# DC309A_PowerSupplies.net
KiCad netlist of a schematic drawn in Altium Designer
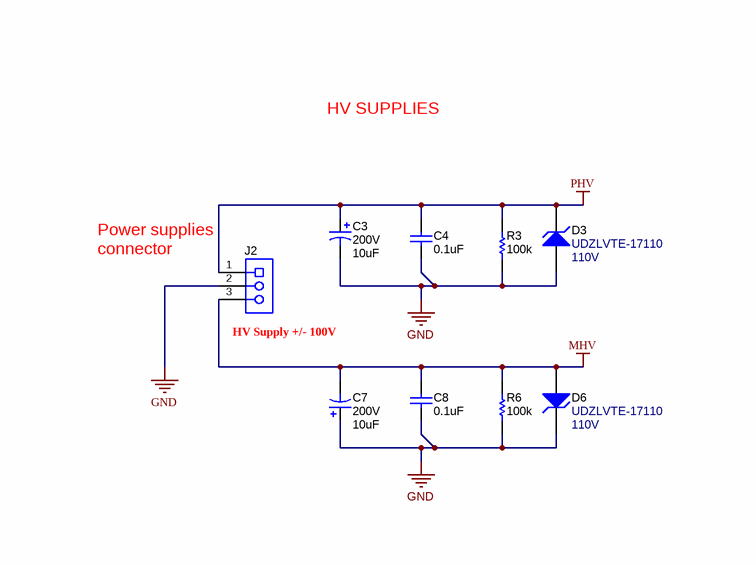
[diagram p0: DC309A_PowerSupplies.SchDoc, top left]
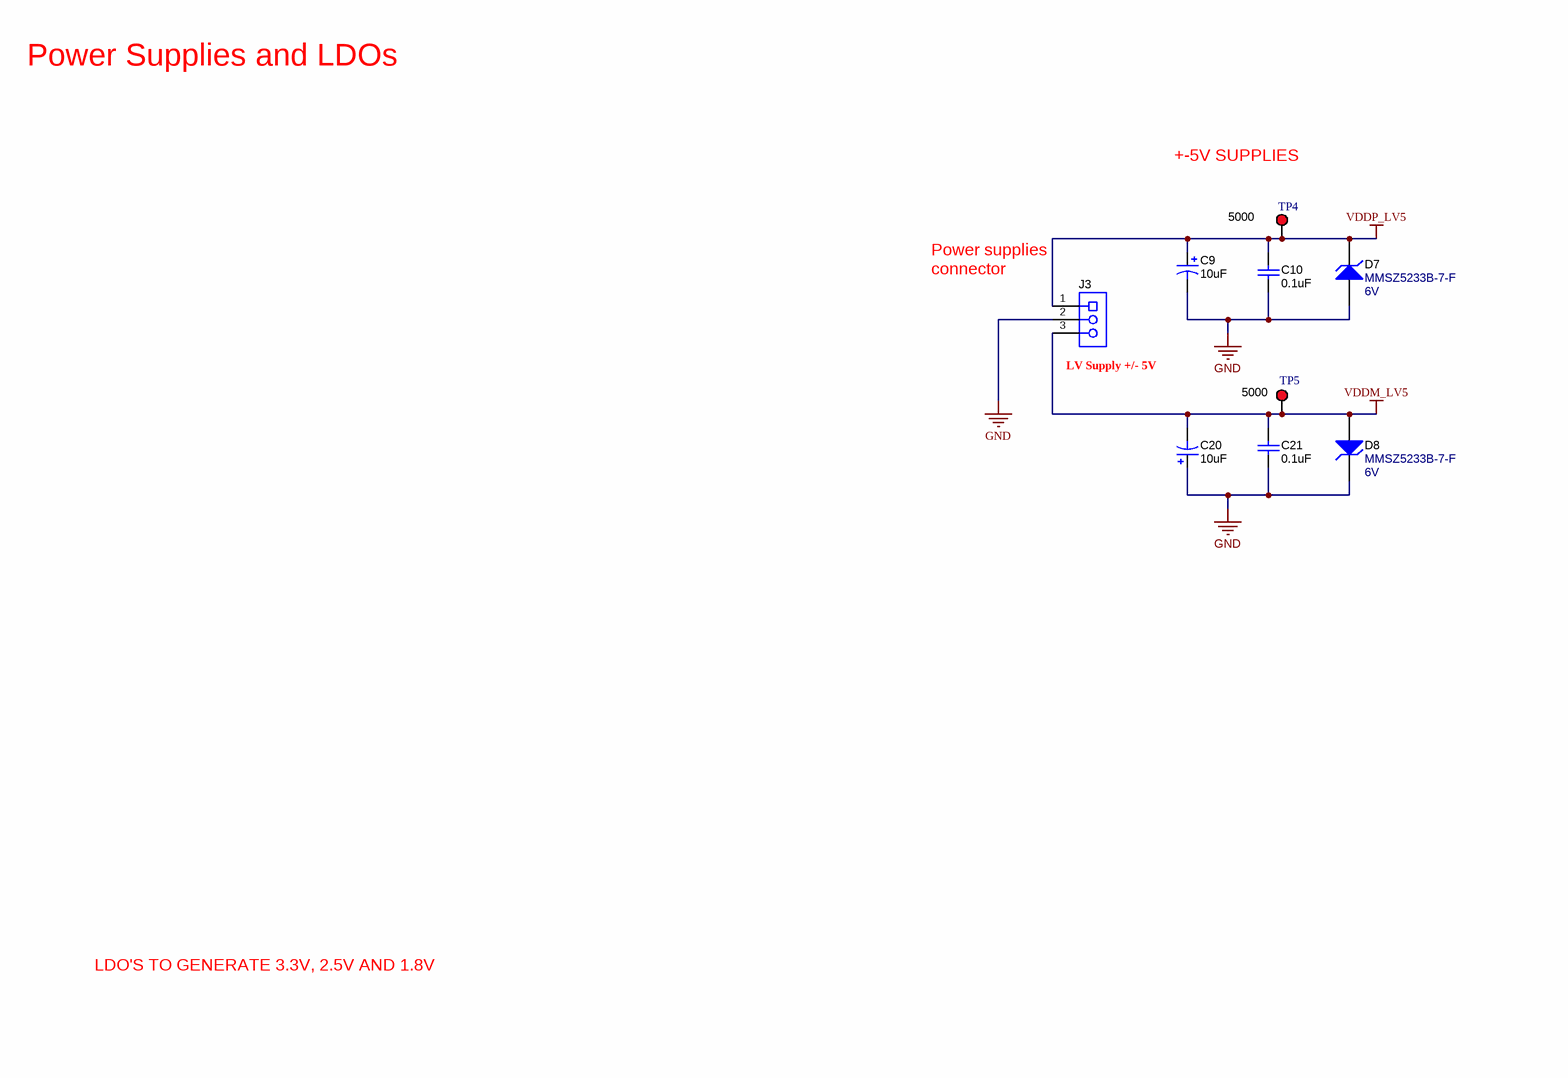
[diagram p1: DC309A_PowerSupplies.SchDoc, top right]
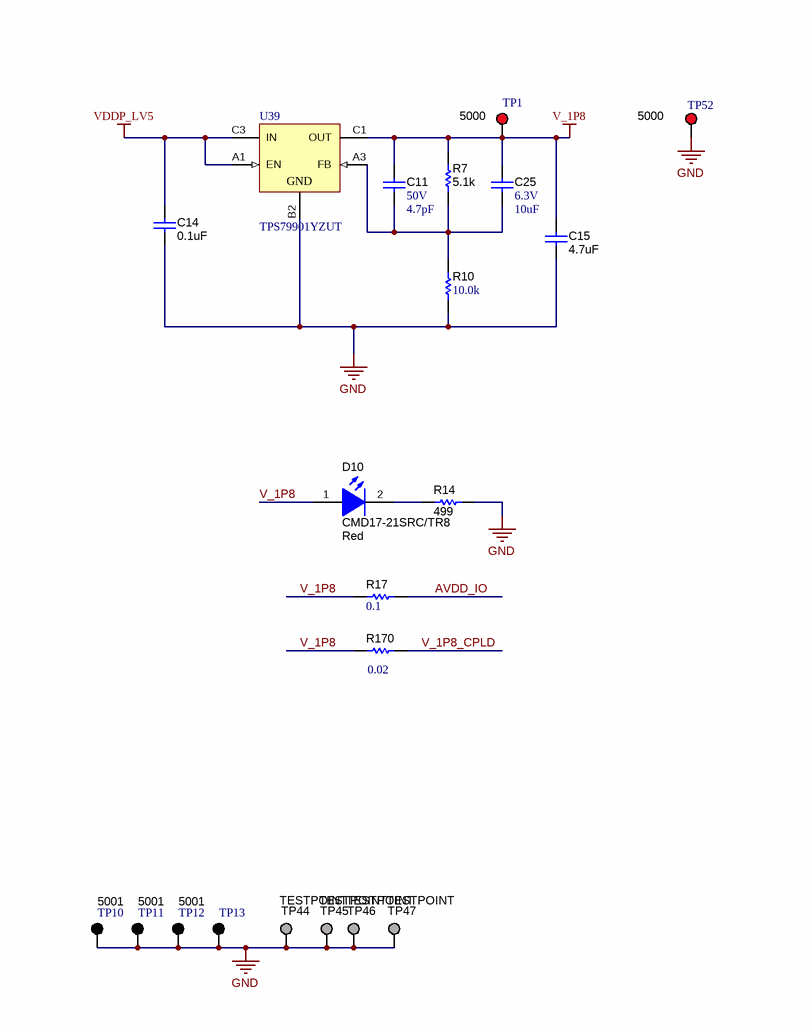
[diagram p2: DC309A_PowerSupplies.SchDoc, bottom left]
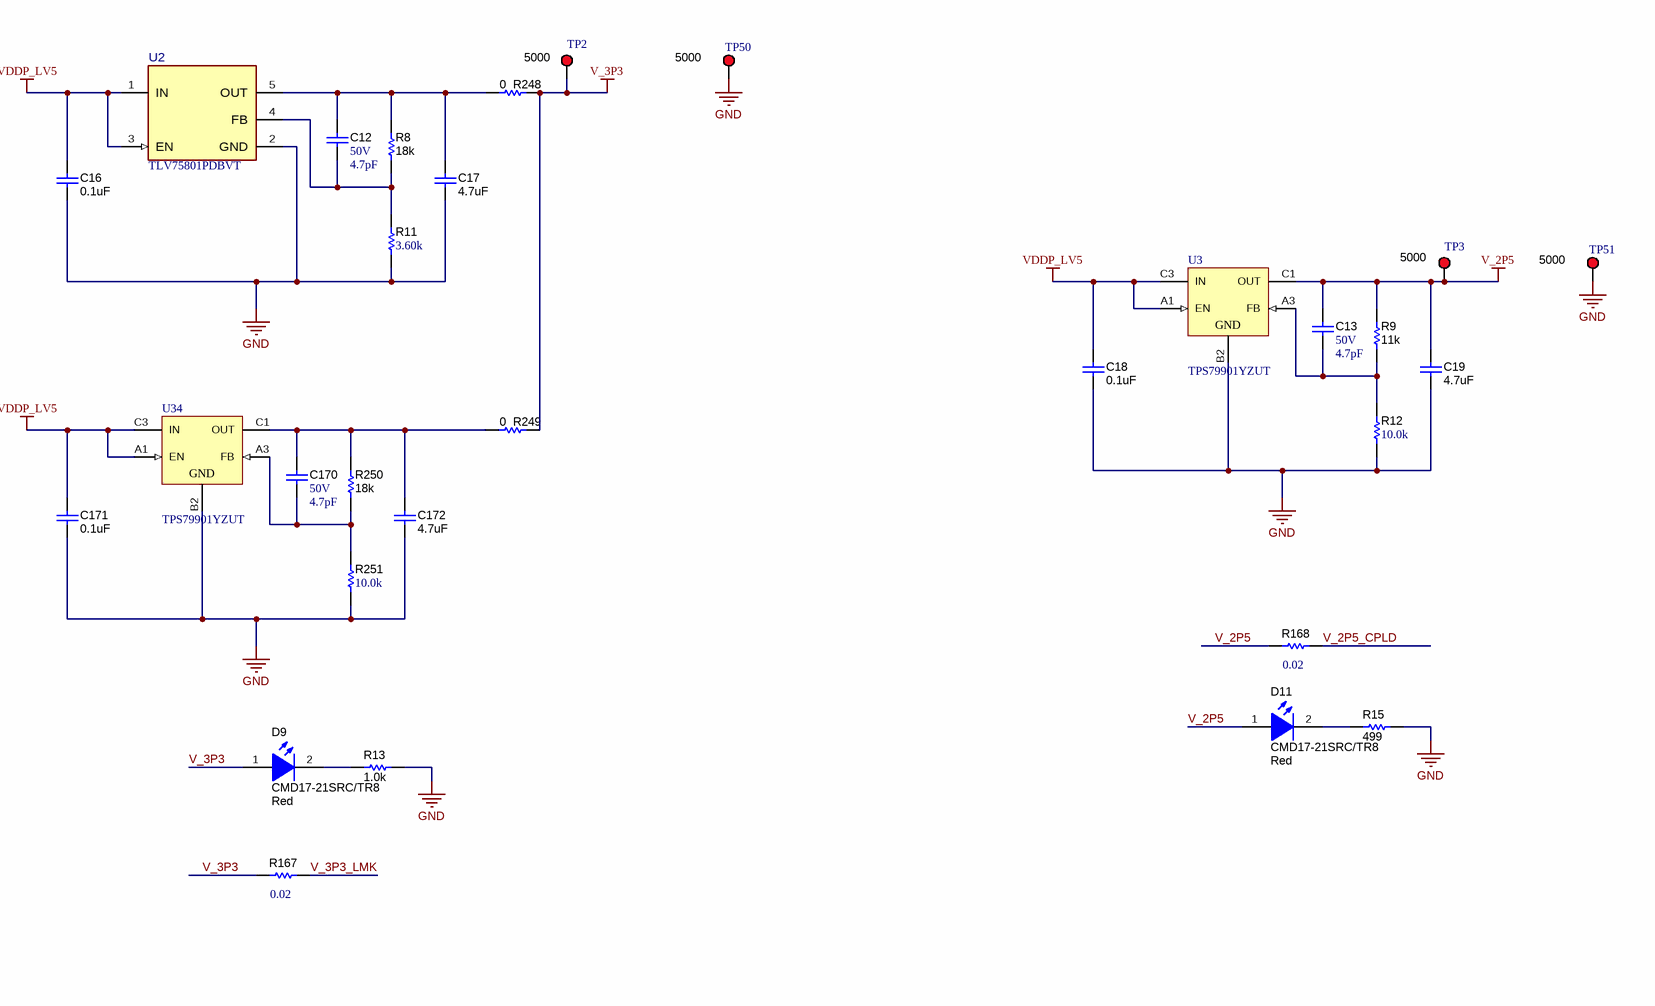
[diagram p3: DC309A_PowerSupplies.SchDoc, bottom right]

(export (version "E")
  (design (tool "Eeschema 10.0.6"))
  (components
    (comp (ref "C3")
      (value "200LLE10MEFC8X11.5")
      (footprint "CAPPRD350W60D800H1150")
      (description "CAP, AL, 10 uF, 200 V, +/- 20%, TH")
      (fields
        (field (name "MANUFACTURER") "Rubycon")
        (field (name "VDC_V") "200V")
        (field (name "VALUEDISPLAYED") "10uF")
        (field (name "PUBLISHER") "Texas Instruments")
      )
      (libsource (lib "Altium Vault - TI") (part "Cap_Polarized"))
    )
    (comp (ref "C4")
      (value "Capacitor")
      (footprint "1206")
      (description "CAP, CERM, 0.1 uF, 200 V, +/- 10%, X7R, 1206")
      (fields
        (field (name "PARTNUMBER") "C1206C104K2RACTU")
        (field (name "VALUEDISPLAYED") "0.1uF")
        (field (name "MANUFACTURER") "Kemet")
        (field (name "PUBLISHER") "Texas Instruments")
      )
      (libsource (lib "Altium Vault - TI") (part "Capacitor"))
    )
    (comp (ref "C7")
      (value "200LLE10MEFC8X11.5")
      (footprint "CAPPRD350W60D800H1150")
      (description "CAP, AL, 10 uF, 200 V, +/- 20%, TH")
      (fields
        (field (name "MANUFACTURER") "Rubycon")
        (field (name "VDC_V") "200V")
        (field (name "VALUEDISPLAYED") "10uF")
        (field (name "PUBLISHER") "Texas Instruments")
      )
      (libsource (lib "Altium Vault - TI") (part "Cap_Polarized"))
    )
    (comp (ref "C8")
      (value "Capacitor")
      (footprint "1206")
      (description "CAP, CERM, 0.1 uF, 200 V, +/- 10%, X7R, 1206")
      (fields
        (field (name "PARTNUMBER") "C1206C104K2RACTU")
        (field (name "VALUEDISPLAYED") "0.1uF")
        (field (name "MANUFACTURER") "Kemet")
        (field (name "PUBLISHER") "Texas Instruments")
      )
      (libsource (lib "Altium Vault - TI") (part "Capacitor"))
    )
    (comp (ref "C9")
      (value "Cap_Polarized")
      (footprint "SM_RADIAL_C")
      (description "CAP, AL, 10 uF, 35 V, +/- 20%, 0.7 ohm, AEC-Q200 Grade 2, SMD")
      (fields
        (field (name "PARTNUMBER") "EEE-FK1V100R")
        (field (name "VALUEDISPLAYED") "10uF")
        (field (name "MANUFACTURER") "Panasonic")
        (field (name "PUBLISHER") "Texas Instruments")
      )
      (libsource (lib "Altium Vault - TI") (part "Cap_Polarized"))
    )
    (comp (ref "C10")
      (value "Capacitor")
      (footprint "0402")
      (description "CAP, CERM, 0.1 uF, 16 V, +/- 10%, X7R, 0402")
      (fields
        (field (name "PARTNUMBER") "0402YC104KAT2A")
        (field (name "VALUEDISPLAYED") "0.1uF")
        (field (name "MANUFACTURER") "AVX")
        (field (name "PUBLISHER") "Texas Instruments")
      )
      (libsource (lib "Altium Vault - TI") (part "Capacitor"))
    )
    (comp (ref "C11")
      (value "06035A4R7CAT2A")
      (footprint "0603")
      (description "CAP, CERM, 4.7 pF, 50 V, +/- 5%, C0G/NP0, 0603")
      (fields
        (field (name "MANUFACTURER") "AVX")
        (field (name "VDC_V") "50V")
        (field (name "VALUEDISPLAYED") "4.7pF")
        (field (name "PUBLISHER") "Texas Instruments")
      )
      (libsource (lib "Altium Vault - TI") (part "Capacitor"))
    )
    (comp (ref "C12")
      (value "06035A4R7CAT2A")
      (footprint "0603")
      (description "CAP, CERM, 4.7 pF, 50 V, +/- 5%, C0G/NP0, 0603")
      (fields
        (field (name "MANUFACTURER") "AVX")
        (field (name "VDC_V") "50V")
        (field (name "VALUEDISPLAYED") "4.7pF")
        (field (name "PUBLISHER") "Texas Instruments")
      )
      (libsource (lib "Altium Vault - TI") (part "Capacitor"))
    )
    (comp (ref "C13")
      (value "06035A4R7CAT2A")
      (footprint "0603")
      (description "CAP, CERM, 4.7 pF, 50 V, +/- 5%, C0G/NP0, 0603")
      (fields
        (field (name "MANUFACTURER") "AVX")
        (field (name "VDC_V") "50V")
        (field (name "VALUEDISPLAYED") "4.7pF")
        (field (name "PUBLISHER") "Texas Instruments")
      )
      (libsource (lib "Altium Vault - TI") (part "Capacitor"))
    )
    (comp (ref "C14")
      (value "Capacitor")
      (footprint "0402")
      (description "CAP, CERM, 0.1 uF, 16 V, +/- 10%, X7R, 0402")
      (fields
        (field (name "PARTNUMBER") "0402YC104KAT2A")
        (field (name "VALUEDISPLAYED") "0.1uF")
        (field (name "MANUFACTURER") "AVX")
        (field (name "PUBLISHER") "Texas Instruments")
      )
      (libsource (lib "Altium Vault - TI") (part "Capacitor"))
    )
    (comp (ref "C15")
      (value "Capacitor")
      (footprint "0805_HV")
      (description "CAP, CERM, 4.7 uF, 25 V, +/- 10%, X5R, 0805")
      (fields
        (field (name "PARTNUMBER") "C0805C475K3PACTU")
        (field (name "VALUEDISPLAYED") "4.7uF")
        (field (name "MANUFACTURER") "Kemet")
        (field (name "PUBLISHER") "Texas Instruments")
      )
      (libsource (lib "") (part "Capacitor_1"))
    )
    (comp (ref "C16")
      (value "Capacitor")
      (footprint "0402")
      (description "CAP, CERM, 0.1 uF, 16 V, +/- 10%, X7R, 0402")
      (fields
        (field (name "PARTNUMBER") "0402YC104KAT2A")
        (field (name "VALUEDISPLAYED") "0.1uF")
        (field (name "MANUFACTURER") "AVX")
        (field (name "PUBLISHER") "Texas Instruments")
      )
      (libsource (lib "Altium Vault - TI") (part "Capacitor"))
    )
    (comp (ref "C17")
      (value "Capacitor")
      (footprint "0805_HV")
      (description "CAP, CERM, 4.7 uF, 25 V, +/- 10%, X5R, 0805")
      (fields
        (field (name "PARTNUMBER") "C0805C475K3PACTU")
        (field (name "VALUEDISPLAYED") "4.7uF")
        (field (name "MANUFACTURER") "Kemet")
        (field (name "PUBLISHER") "Texas Instruments")
      )
      (libsource (lib "Altium Vault - TI") (part "CMP-0007800-2"))
    )
    (comp (ref "C18")
      (value "Capacitor")
      (footprint "0402")
      (description "CAP, CERM, 0.1 uF, 16 V, +/- 10%, X7R, 0402")
      (fields
        (field (name "PARTNUMBER") "0402YC104KAT2A")
        (field (name "VALUEDISPLAYED") "0.1uF")
        (field (name "MANUFACTURER") "AVX")
        (field (name "PUBLISHER") "Texas Instruments")
      )
      (libsource (lib "Altium Vault - TI") (part "Capacitor"))
    )
    (comp (ref "C19")
      (value "Capacitor")
      (footprint "0805_HV")
      (description "CAP, CERM, 4.7 uF, 25 V, +/- 10%, X5R, 0805")
      (fields
        (field (name "PARTNUMBER") "C0805C475K3PACTU")
        (field (name "VALUEDISPLAYED") "4.7uF")
        (field (name "MANUFACTURER") "Kemet")
        (field (name "PUBLISHER") "Texas Instruments")
      )
      (libsource (lib "Altium Vault - TI") (part "Capacitor"))
    )
    (comp (ref "C20")
      (value "Cap_Polarized")
      (footprint "SM_RADIAL_C")
      (description "CAP, AL, 10 uF, 35 V, +/- 20%, 0.7 ohm, AEC-Q200 Grade 2, SMD")
      (fields
        (field (name "PARTNUMBER") "EEE-FK1V100R")
        (field (name "VALUEDISPLAYED") "10uF")
        (field (name "MANUFACTURER") "Panasonic")
        (field (name "PUBLISHER") "Texas Instruments")
      )
      (libsource (lib "Altium Vault - TI") (part "Cap_Polarized"))
    )
    (comp (ref "C21")
      (value "Capacitor")
      (footprint "0402")
      (description "CAP, CERM, 0.1 uF, 16 V, +/- 10%, X7R, 0402")
      (fields
        (field (name "PARTNUMBER") "0402YC104KAT2A")
        (field (name "VALUEDISPLAYED") "0.1uF")
        (field (name "MANUFACTURER") "AVX")
        (field (name "PUBLISHER") "Texas Instruments")
      )
      (libsource (lib "Altium Vault - TI") (part "Capacitor"))
    )
    (comp (ref "C25")
      (value "GRM188R60J106ME47D")
      (footprint "0603")
      (description "CAP, CERM, 10 uF, 6.3 V, +/- 20%, X5R, 0603")
      (fields
        (field (name "MANUFACTURER") "MuRata")
        (field (name "VDC_V") "6.3V")
        (field (name "VALUEDISPLAYED") "10uF")
        (field (name "PUBLISHER") "Texas Instruments")
      )
      (libsource (lib "Altium Vault - TI") (part "Capacitor"))
    )
    (comp (ref "C170")
      (value "06035A4R7CAT2A")
      (footprint "0603")
      (description "CAP, CERM, 4.7 pF, 50 V, +/- 5%, C0G/NP0, 0603")
      (fields
        (field (name "MANUFACTURER") "AVX")
        (field (name "VDC_V") "50V")
        (field (name "VALUEDISPLAYED") "4.7pF")
        (field (name "PUBLISHER") "Texas Instruments")
      )
      (libsource (lib "Altium Vault - TI") (part "Capacitor"))
    )
    (comp (ref "C171")
      (value "Capacitor")
      (footprint "0402")
      (description "CAP, CERM, 0.1 uF, 16 V, +/- 10%, X7R, 0402")
      (fields
        (field (name "PARTNUMBER") "0402YC104KAT2A")
        (field (name "VALUEDISPLAYED") "0.1uF")
        (field (name "MANUFACTURER") "AVX")
        (field (name "PUBLISHER") "Texas Instruments")
      )
      (libsource (lib "Altium Vault - TI") (part "Capacitor"))
    )
    (comp (ref "C172")
      (value "Capacitor")
      (footprint "0805_HV")
      (description "CAP, CERM, 4.7 uF, 25 V, +/- 10%, X5R, 0805")
      (fields
        (field (name "PARTNUMBER") "C0805C475K3PACTU")
        (field (name "VALUEDISPLAYED") "4.7uF")
        (field (name "MANUFACTURER") "Kemet")
        (field (name "PUBLISHER") "Texas Instruments")
      )
      (libsource (lib "Altium Vault - TI") (part "Capacitor"))
    )
    (comp (ref "D3")
      (value "UDZLVTE-17110")
      (footprint "SOD-323F")
      (description "Diode, Zener, 110 V, 200 mW, SOD-323F")
      (fields (field (name "ALTIUM_VALUE") "110V") (field (name "MANUFACTURER") "Rohm"))
      (libsource (lib "Altium Vault - TI") (part "Zener"))
    )
    (comp (ref "D6")
      (value "UDZLVTE-17110")
      (footprint "SOD-323F")
      (description "Diode, Zener, 110 V, 200 mW, SOD-323F")
      (fields (field (name "ALTIUM_VALUE") "110V") (field (name "MANUFACTURER") "Rohm"))
      (libsource (lib "Altium Vault - TI") (part "Zener"))
    )
    (comp (ref "D7")
      (value "MMSZ5233B-7-F")
      (footprint "SOD-123")
      (description "Diode, Zener, 6 V, 500 mW, SOD-123")
      (fields (field (name "ALTIUM_VALUE") "6V") (field (name "MANUFACTURER") "Diodes Inc."))
      (libsource (lib "Altium Vault - TI") (part "Zener"))
    )
    (comp (ref "D8")
      (value "MMSZ5233B-7-F")
      (footprint "SOD-123")
      (description "Diode, Zener, 6 V, 500 mW, SOD-123")
      (fields (field (name "ALTIUM_VALUE") "6V") (field (name "MANUFACTURER") "Diodes Inc."))
      (libsource (lib "Altium Vault - TI") (part "Zener"))
    )
    (comp (ref "D9")
      (value "CMD17-21SRC/TR8")
      (footprint "CMD17-21_Red")
      (description "LED, Red, SMD")
      (fields
        (field (name "ALTIUM_VALUE") "Red")
        (field (name "MANUFACTURER") "Visual Communications Company, LLC")
      )
      (libsource (lib "Altium Vault - TI") (part "LED"))
    )
    (comp (ref "D10")
      (value "CMD17-21SRC/TR8")
      (footprint "CMD17-21_Red")
      (description "LED, Red, SMD")
      (fields
        (field (name "ALTIUM_VALUE") "Red")
        (field (name "MANUFACTURER") "Visual Communications Company, LLC")
      )
      (libsource (lib "Altium Vault - TI") (part "LED"))
    )
    (comp (ref "D11")
      (value "CMD17-21SRC/TR8")
      (footprint "CMD17-21_Red")
      (description "LED, Red, SMD")
      (fields
        (field (name "ALTIUM_VALUE") "Red")
        (field (name "MANUFACTURER") "Visual Communications Company, LLC")
      )
      (libsource (lib "Altium Vault - TI") (part "LED"))
    )
    (comp (ref "J2")
      (value "1725669")
      (footprint "Phoenix_1725669")
      (description "Terminal Block, 3x1, 2.54 mm, TH")
      (fields (field (name "MANUFACTURER") "Phoenix Contact") (field (name "PUBLISHER") "Texas Instruments"))
      (libsource (lib "Altium Vault - TI") (part "CMP-0055500-1"))
    )
    (comp (ref "J3")
      (value "1725669")
      (footprint "Phoenix_1725669")
      (description "Terminal Block, 3x1, 2.54 mm, TH")
      (fields (field (name "MANUFACTURER") "Phoenix Contact") (field (name "PUBLISHER") "Texas Instruments"))
      (libsource (lib "Altium Vault - TI") (part "CMP-0055500-1"))
    )
    (comp (ref "R3")
      (value "Resistor")
      (footprint "1206")
      (description "RES, 100 k, 0.1%, 0.25 W, AEC-Q200 Grade 1, 1206")
      (fields
        (field (name "PARTNUMBER") "TNPW1206100KBEEA")
        (field (name "VALUEDISPLAYED") "100k")
        (field (name "MANUFACTURER") "Vishay-Dale")
        (field (name "PUBLISHER") "Texas Instruments")
      )
      (libsource (lib "Altium Vault - TI") (part "CMP-0018819-2"))
    )
    (comp (ref "R6")
      (value "Resistor")
      (footprint "1206")
      (description "RES, 100 k, 0.1%, 0.25 W, AEC-Q200 Grade 1, 1206")
      (fields
        (field (name "PARTNUMBER") "TNPW1206100KBEEA")
        (field (name "VALUEDISPLAYED") "100k")
        (field (name "MANUFACTURER") "Vishay-Dale")
        (field (name "PUBLISHER") "Texas Instruments")
      )
      (libsource (lib "Altium Vault - TI") (part "Resistor"))
    )
    (comp (ref "R7")
      (value "CMP-0026951-5")
      (footprint "0402")
      (description "RES, 5.1 k, 5%, 0.063 W, AEC-Q200 Grade 0, 0402")
      (fields
        (field (name "PARTNUMBER") "CRCW04025K10JNED")
        (field (name "VALUEDISPLAYED") "5.1k")
        (field (name "MANUFACTURER") "Vishay-Dale")
      )
      (libsource (lib "Altium Vault - TI") (part "Resistor"))
    )
    (comp (ref "R8")
      (value "CRCW040218K0JNED")
      (footprint "0402")
      (description "RES, 18 k, 5%, 0.063 W, AEC-Q200 Grade 0, 0402")
      (fields (field (name "MANUFACTURER") "Vishay-Dale") (field (name "VALUEDISPLAYED") "18k"))
      (libsource (lib "Altium Vault - TI") (part "CMP-0026850-3"))
    )
    (comp (ref "R9")
      (value "Resistor")
      (footprint "0402")
      (description "RES, 11 k, 5%, 0.063 W, AEC-Q200 Grade 0, 0402")
      (fields
        (field (name "PARTNUMBER") "CRCW040211K0JNED")
        (field (name "VALUEDISPLAYED") "11k")
        (field (name "MANUFACTURER") "Vishay-Dale")
      )
      (libsource (lib "Altium Vault - TI") (part "Resistor"))
    )
    (comp (ref "R10")
      (value "CRCW040210K0DHEDP")
      (footprint "0402")
      (description "RES, 10.0 k, 0.5%, 0.063 W, AEC-Q200 Grade 0, 0402")
      (fields (field (name "MANUFACTURER") "Vishay-Dale") (field (name "VALUEDISPLAYED") "10.0k"))
      (libsource (lib "Altium Vault - TI") (part "Resistor"))
    )
    (comp (ref "R11")
      (value "RG1608P-362-B-T5")
      (footprint "0603")
      (description "RES, 3.60 k, 0.1%, 0.1 W, 0603")
      (fields
        (field (name "MANUFACTURER") "Susumu Co Ltd")
        (field (name "VALUEDISPLAYED") "3.60k")
        (field (name "PUBLISHER") "Texas Instruments")
      )
      (libsource (lib "Altium Vault - TI") (part "Resistor"))
    )
    (comp (ref "R12")
      (value "CRCW040210K0DHEDP")
      (footprint "0402")
      (description "RES, 10.0 k, 0.5%, 0.063 W, AEC-Q200 Grade 0, 0402")
      (fields (field (name "MANUFACTURER") "Vishay-Dale") (field (name "VALUEDISPLAYED") "10.0k"))
      (libsource (lib "Altium Vault - TI") (part "Resistor"))
    )
    (comp (ref "R13")
      (value "Resistor")
      (footprint "0402")
      (description "RES, 1.0 k, 5%, 0.063 W, AEC-Q200 Grade 0, 0402")
      (fields
        (field (name "PARTNUMBER") "CRCW04021K00JNED")
        (field (name "VALUEDISPLAYED") "1.0k")
        (field (name "MANUFACTURER") "Vishay-Dale")
      )
      (libsource (lib "Altium Vault - TI") (part "Resistor"))
    )
    (comp (ref "R14")
      (value "Resistor")
      (footprint "0402")
      (description "RES, 499, 1%, 0.063 W, AEC-Q200 Grade 0, 0402")
      (fields
        (field (name "PARTNUMBER") "CRCW0402499RFKED")
        (field (name "VALUEDISPLAYED") "499")
        (field (name "MANUFACTURER") "Vishay-Dale")
      )
      (libsource (lib "Altium Vault - TI") (part "Resistor"))
    )
    (comp (ref "R15")
      (value "Resistor")
      (footprint "0402")
      (description "RES, 499, 1%, 0.063 W, AEC-Q200 Grade 0, 0402")
      (fields
        (field (name "PARTNUMBER") "CRCW0402499RFKED")
        (field (name "VALUEDISPLAYED") "499")
        (field (name "MANUFACTURER") "Vishay-Dale")
      )
      (libsource (lib "Altium Vault - TI") (part "Resistor"))
    )
    (comp (ref "R17")
      (value "ERJ-L03KF10CV")
      (footprint "0603")
      (description "RES, 0.1, 1%, 0.1 W, AEC-Q200 Grade 1, 0603")
      (fields (field (name "MANUFACTURER") "Panasonic") (field (name "VALUEDISPLAYED") "0.1"))
      (libsource (lib "Altium Vault - TI") (part "Resistor"))
    )
    (comp (ref "R167")
      (value "RL0603FR-070R02L")
      (footprint "0603")
      (description "RES, 0.02, 1%, 0.1 W, AEC-Q200 Grade 0, 0603")
      (fields
        (field (name "MANUFACTURER") "Yageo America")
        (field (name "RES_OHM") "0.02")
        (field (name "PUBLISHER") "Texas Instruments")
      )
      (libsource (lib "Altium Vault - TI") (part "Resistor"))
    )
    (comp (ref "R168")
      (value "RL0603FR-070R02L")
      (footprint "0603")
      (description "RES, 0.02, 1%, 0.1 W, AEC-Q200 Grade 0, 0603")
      (fields
        (field (name "MANUFACTURER") "Yageo America")
        (field (name "RES_OHM") "0.02")
        (field (name "PUBLISHER") "Texas Instruments")
      )
      (libsource (lib "Altium Vault - TI") (part "Resistor"))
    )
    (comp (ref "R170")
      (value "RL0603FR-070R02L")
      (footprint "0603")
      (description "RES, 0.02, 1%, 0.1 W, AEC-Q200 Grade 0, 0603")
      (fields
        (field (name "MANUFACTURER") "Yageo America")
        (field (name "RES_OHM") "0.02")
        (field (name "PUBLISHER") "Texas Instruments")
      )
      (libsource (lib "Altium Vault - TI") (part "Resistor"))
    )
    (comp (ref "R248")
      (value "Resistor")
      (footprint "0402")
      (description "RES, 0, 5%, 0.1 W, AEC-Q200 Grade 0, 0402")
      (fields
        (field (name "PARTNUMBER") "ERJ-2GE0R00X")
        (field (name "MANUFACTURER") "Panasonic")
        (field (name "RES_OHM") "0")
      )
      (libsource (lib "Altium Vault - TI") (part "CMP-0026992-3"))
    )
    (comp (ref "R249")
      (value "Resistor")
      (footprint "0402")
      (description "RES, 0, 5%, 0.1 W, AEC-Q200 Grade 0, 0402")
      (fields
        (field (name "PARTNUMBER") "ERJ-2GE0R00X")
        (field (name "MANUFACTURER") "Panasonic")
        (field (name "RES_OHM") "0")
      )
      (libsource (lib "Altium Vault - TI") (part "CMP-0026992-3"))
    )
    (comp (ref "R250")
      (value "CRCW040218K0JNED")
      (footprint "0402")
      (description "RES, 18 k, 5%, 0.063 W, AEC-Q200 Grade 0, 0402")
      (fields (field (name "MANUFACTURER") "Vishay-Dale") (field (name "VALUEDISPLAYED") "18k"))
      (libsource (lib "Altium Vault - TI") (part "CMP-0026850-3"))
    )
    (comp (ref "R251")
      (value "CRCW040210K0DHEDP")
      (footprint "0402")
      (description "RES, 10.0 k, 0.5%, 0.063 W, AEC-Q200 Grade 0, 0402")
      (fields (field (name "MANUFACTURER") "Vishay-Dale") (field (name "VALUEDISPLAYED") "10.0k"))
      (libsource (lib "Altium Vault - TI") (part "Resistor"))
    )
    (comp (ref "TP1")
      (value "5000")
      (footprint "Keystone5000")
      (description "Test Point, Miniature, Red, TH")
      (fields
        (field (name "MANUFACTURER") "Keystone Electronics")
        (field (name "PUBLISHER") "Texas Instruments")
      )
      (libsource (lib "Altium Vault - TI") (part "5000"))
    )
    (comp (ref "TP2")
      (value "5000")
      (footprint "Keystone5000")
      (description "Test Point, Miniature, Red, TH")
      (fields
        (field (name "MANUFACTURER") "Keystone Electronics")
        (field (name "PUBLISHER") "Texas Instruments")
      )
      (libsource (lib "Altium Vault - TI") (part "5000"))
    )
    (comp (ref "TP3")
      (value "5000")
      (footprint "Keystone5000")
      (description "Test Point, Miniature, Red, TH")
      (fields
        (field (name "MANUFACTURER") "Keystone Electronics")
        (field (name "PUBLISHER") "Texas Instruments")
      )
      (libsource (lib "Altium Vault - TI") (part "5000"))
    )
    (comp (ref "TP4")
      (value "5000")
      (footprint "Keystone5000")
      (description "Test Point, Miniature, Red, TH")
      (fields
        (field (name "MANUFACTURER") "Keystone Electronics")
        (field (name "PUBLISHER") "Texas Instruments")
      )
      (libsource (lib "Altium Vault - TI") (part "5000"))
    )
    (comp (ref "TP5")
      (value "5000")
      (footprint "Keystone5000")
      (description "Test Point, Miniature, Red, TH")
      (fields
        (field (name "MANUFACTURER") "Keystone Electronics")
        (field (name "PUBLISHER") "Texas Instruments")
      )
      (libsource (lib "Altium Vault - TI") (part "5000"))
    )
    (comp (ref "TP10")
      (value "5001")
      (footprint "Keystone5001")
      (description "Test Point, Miniature, Black, TH")
      (fields
        (field (name "MANUFACTURER") "Keystone Electronics")
        (field (name "PUBLISHER") "Texas Instruments")
      )
      (libsource (lib "Altium Vault - TI") (part "5001"))
    )
    (comp (ref "TP11")
      (value "5001")
      (footprint "Keystone5001")
      (description "Test Point, Miniature, Black, TH")
      (fields
        (field (name "MANUFACTURER") "Keystone Electronics")
        (field (name "PUBLISHER") "Texas Instruments")
      )
      (libsource (lib "Altium Vault - TI") (part "5001"))
    )
    (comp (ref "TP12")
      (value "5001")
      (footprint "Keystone5001")
      (description "Test Point, Miniature, Black, TH")
      (fields
        (field (name "MANUFACTURER") "Keystone Electronics")
        (field (name "PUBLISHER") "Texas Instruments")
      )
      (libsource (lib "Altium Vault - TI") (part "5001"))
    )
    (comp (ref "TP13")
      (value "5001")
      (footprint "Keystone5001")
      (description "Test Point, Miniature, Black, TH")
      (fields
        (field (name "MANUFACTURER") "Keystone Electronics")
        (field (name "PUBLISHER") "Texas Instruments")
      )
      (libsource (lib "Altium Vault - TI") (part "5001"))
    )
    (comp (ref "TP44")
      (value "TESTPOINT")
      (footprint "TP_50MIL-SMT")
      (description "TEST POINT.  No entry in BOM.")
      (libsource (lib "Altium Vault - TI") (part "TESTPOINT"))
    )
    (comp (ref "TP45")
      (value "TESTPOINT")
      (footprint "TP_50MIL-SMT")
      (description "TEST POINT.  No entry in BOM.")
      (libsource (lib "Altium Vault - TI") (part "TESTPOINT"))
    )
    (comp (ref "TP46")
      (value "TESTPOINT")
      (footprint "TP_50MIL-SMT")
      (description "TEST POINT.  No entry in BOM.")
      (libsource (lib "Altium Vault - TI") (part "TESTPOINT"))
    )
    (comp (ref "TP47")
      (value "TESTPOINT")
      (footprint "TP_50MIL-SMT")
      (description "TEST POINT.  No entry in BOM.")
      (libsource (lib "Altium Vault - TI") (part "TESTPOINT"))
    )
    (comp (ref "TP50")
      (value "5000")
      (footprint "Keystone5000")
      (description "Test Point, Miniature, Red, TH")
      (fields
        (field (name "MANUFACTURER") "Keystone Electronics")
        (field (name "PUBLISHER") "Texas Instruments")
      )
      (libsource (lib "Altium Vault - TI") (part "5000"))
    )
    (comp (ref "TP51")
      (value "5000")
      (footprint "Keystone5000")
      (description "Test Point, Miniature, Red, TH")
      (fields
        (field (name "MANUFACTURER") "Keystone Electronics")
        (field (name "PUBLISHER") "Texas Instruments")
      )
      (libsource (lib "Altium Vault - TI") (part "5000"))
    )
    (comp (ref "TP52")
      (value "5000")
      (footprint "Keystone5000")
      (description "Test Point, Miniature, Red, TH")
      (fields
        (field (name "MANUFACTURER") "Keystone Electronics")
        (field (name "PUBLISHER") "Texas Instruments")
      )
      (libsource (lib "Altium Vault - TI") (part "5000"))
    )
    (comp (ref "U2")
      (value "TLV75801PDBVT")
      (footprint "DBV0005A-MFG")
      (description "Linear Voltage Regulator IC  1 Output  500mA SOT-23-5")
      (fields
        (field (name "PARTNUMBER") "TLV75801PDBVT")
        (field (name "DIGIKEY PART NUMBER") "296-TLV75801PDBVTCT-ND")
        (field (name "MOUSER PART NUMBER") "595-TLV75801PDBVT")
      )
      (libsource (lib "Altium Vault - TI") (part "SYM-TLV75801PDBVT"))
    )
    (comp (ref "U3")
      (value "TPS79901YZUT")
      (footprint "YZU0005AEBC")
      (fields (field (name "MANUFACTURER") "Texas Instruments"))
      (libsource (lib "Altium Content Vault") (part "TI-TPS79901YZU5"))
    )
    (comp (ref "U34")
      (value "TPS79901YZUT")
      (footprint "YZU0005AEBC")
      (fields (field (name "MANUFACTURER") "Texas Instruments"))
      (libsource (lib "Altium Content Vault") (part "TI-TPS79901YZU5"))
    )
    (comp (ref "U39")
      (value "TPS79901YZUT")
      (footprint "YZU0005AEBC")
      (fields (field (name "MANUFACTURER") "Texas Instruments"))
      (libsource (lib "Altium Content Vault") (part "TI-TPS79901YZU5"))
    )
  )
  (nets
    (net (code "1") (name "/AVDD_IO") (class "Default")
      (node (ref "R17") (pin "2") (pinfunction "2_2") (pintype "passive"))
    )
    (net (code "2") (name "/V_1P8_CPLD") (class "Default")
      (node (ref "R170") (pin "2") (pinfunction "2_2") (pintype "passive"))
    )
    (net (code "3") (name "/V_2P5_CPLD") (class "Default")
      (node (ref "R168") (pin "2") (pinfunction "2_2") (pintype "passive"))
    )
    (net (code "4") (name "/V_3P3_LMK") (class "Default")
      (node (ref "R167") (pin "2") (pinfunction "2_2") (pintype "passive"))
    )
    (net (code "5") (name "GND") (class "Default")
      (node (ref "C10") (pin "2") (pinfunction "2_2") (pintype "passive"))
      (node (ref "C14") (pin "2") (pinfunction "2_2") (pintype "passive"))
      (node (ref "C15") (pin "1") (pinfunction "1_1") (pintype "passive"))
      (node (ref "C16") (pin "2") (pinfunction "2_2") (pintype "passive"))
      (node (ref "C17") (pin "2") (pinfunction "2_2") (pintype "passive"))
      (node (ref "C171") (pin "2") (pinfunction "2_2") (pintype "passive"))
      (node (ref "C172") (pin "2") (pinfunction "2_2") (pintype "passive"))
      (node (ref "C18") (pin "2") (pinfunction "2_2") (pintype "passive"))
      (node (ref "C19") (pin "2") (pinfunction "2_2") (pintype "passive"))
      (node (ref "C20") (pin "1") (pinfunction "+_1") (pintype "passive"))
      (node (ref "C21") (pin "2") (pinfunction "2_2") (pintype "passive"))
      (node (ref "C3") (pin "2") (pinfunction "-_2") (pintype "passive"))
      (node (ref "C4") (pin "2") (pinfunction "2_2") (pintype "passive"))
      (node (ref "C7") (pin "1") (pinfunction "+_1") (pintype "passive"))
      (node (ref "C8") (pin "2") (pinfunction "2_2") (pintype "passive"))
      (node (ref "C9") (pin "2") (pinfunction "-_2") (pintype "passive"))
      (node (ref "D3") (pin "2") (pinfunction "A_2") (pintype "passive"))
      (node (ref "D6") (pin "1") (pinfunction "K_1") (pintype "passive"))
      (node (ref "D7") (pin "2") (pinfunction "A_2") (pintype "passive"))
      (node (ref "D8") (pin "1") (pinfunction "K_1") (pintype "passive"))
      (node (ref "J2") (pin "2") (pinfunction "2_2") (pintype "passive"))
      (node (ref "J3") (pin "2") (pinfunction "2_2") (pintype "passive"))
      (node (ref "R10") (pin "1") (pinfunction "1_1") (pintype "passive"))
      (node (ref "R11") (pin "1") (pinfunction "1_1") (pintype "passive"))
      (node (ref "R12") (pin "1") (pinfunction "1_1") (pintype "passive"))
      (node (ref "R13") (pin "2") (pinfunction "2_2") (pintype "passive"))
      (node (ref "R14") (pin "2") (pinfunction "2_2") (pintype "passive"))
      (node (ref "R15") (pin "2") (pinfunction "2_2") (pintype "passive"))
      (node (ref "R251") (pin "1") (pinfunction "1_1") (pintype "passive"))
      (node (ref "R3") (pin "1") (pinfunction "1_1") (pintype "passive"))
      (node (ref "R6") (pin "1") (pinfunction "1_1") (pintype "passive"))
      (node (ref "TP10") (pin "1") (pintype "passive"))
      (node (ref "TP11") (pin "1") (pintype "passive"))
      (node (ref "TP12") (pin "1") (pintype "passive"))
      (node (ref "TP13") (pin "1") (pintype "passive"))
      (node (ref "TP44") (pin "1") (pintype "passive"))
      (node (ref "TP45") (pin "1") (pintype "passive"))
      (node (ref "TP46") (pin "1") (pintype "passive"))
      (node (ref "TP47") (pin "1") (pintype "passive"))
      (node (ref "TP50") (pin "1") (pintype "passive"))
      (node (ref "TP51") (pin "1") (pintype "passive"))
      (node (ref "TP52") (pin "1") (pintype "passive"))
      (node (ref "U2") (pin "2") (pinfunction "GND_2") (pintype "power_in"))
      (node (ref "U3") (pin "B2") (pinfunction "GND_B2") (pintype "power_in"))
      (node (ref "U34") (pin "B2") (pinfunction "GND_B2") (pintype "power_in"))
      (node (ref "U39") (pin "B2") (pinfunction "GND_B2") (pintype "power_in"))
    )
    (net (code "6") (name "MHV") (class "Default")
      (node (ref "C7") (pin "2") (pinfunction "-_2") (pintype "passive"))
      (node (ref "C8") (pin "1") (pinfunction "1_1") (pintype "passive"))
      (node (ref "D6") (pin "2") (pinfunction "A_2") (pintype "passive"))
      (node (ref "J2") (pin "3") (pinfunction "3_3") (pintype "passive"))
      (node (ref "R6") (pin "2") (pinfunction "2_2") (pintype "passive"))
    )
    (net (code "7") (name "Net-(D9-K)") (class "Default")
      (node (ref "D9") (pin "2") (pinfunction "K_2") (pintype "passive"))
      (node (ref "R13") (pin "1") (pinfunction "1_1") (pintype "passive"))
    )
    (net (code "8") (name "Net-(D10-K)") (class "Default")
      (node (ref "D10") (pin "2") (pinfunction "K_2") (pintype "passive"))
      (node (ref "R14") (pin "1") (pinfunction "1_1") (pintype "passive"))
    )
    (net (code "9") (name "Net-(D11-K)") (class "Default")
      (node (ref "D11") (pin "2") (pinfunction "K_2") (pintype "passive"))
      (node (ref "R15") (pin "1") (pinfunction "1_1") (pintype "passive"))
    )
    (net (code "10") (name "Net-(U2-FB)") (class "Default")
      (node (ref "C12") (pin "2") (pinfunction "2_2") (pintype "passive"))
      (node (ref "R11") (pin "2") (pinfunction "2_2") (pintype "passive"))
      (node (ref "R8") (pin "1") (pinfunction "1_1") (pintype "passive"))
      (node (ref "U2") (pin "4") (pinfunction "FB_4") (pintype "passive"))
    )
    (net (code "11") (name "Net-(U2-OUT)") (class "Default")
      (node (ref "C12") (pin "1") (pinfunction "1_1") (pintype "passive"))
      (node (ref "C17") (pin "1") (pinfunction "1_1") (pintype "passive"))
      (node (ref "R248") (pin "1") (pinfunction "1_1") (pintype "passive"))
      (node (ref "R8") (pin "2") (pinfunction "2_2") (pintype "passive"))
      (node (ref "U2") (pin "5") (pinfunction "OUT_5") (pintype "power_in"))
    )
    (net (code "12") (name "Net-(U3-FB)") (class "Default")
      (node (ref "C13") (pin "2") (pinfunction "2_2") (pintype "passive"))
      (node (ref "R12") (pin "2") (pinfunction "2_2") (pintype "passive"))
      (node (ref "R9") (pin "1") (pinfunction "1_1") (pintype "passive"))
      (node (ref "U3") (pin "A3") (pinfunction "FB_A3") (pintype "input"))
    )
    (net (code "13") (name "Net-(U34-FB)") (class "Default")
      (node (ref "C170") (pin "2") (pinfunction "2_2") (pintype "passive"))
      (node (ref "R250") (pin "1") (pinfunction "1_1") (pintype "passive"))
      (node (ref "R251") (pin "2") (pinfunction "2_2") (pintype "passive"))
      (node (ref "U34") (pin "A3") (pinfunction "FB_A3") (pintype "input"))
    )
    (net (code "14") (name "Net-(U34-OUT)") (class "Default")
      (node (ref "C170") (pin "1") (pinfunction "1_1") (pintype "passive"))
      (node (ref "C172") (pin "1") (pinfunction "1_1") (pintype "passive"))
      (node (ref "R249") (pin "1") (pinfunction "1_1") (pintype "passive"))
      (node (ref "R250") (pin "2") (pinfunction "2_2") (pintype "passive"))
      (node (ref "U34") (pin "C1") (pinfunction "OUT_C1") (pintype "power_in"))
    )
    (net (code "15") (name "Net-(U39-FB)") (class "Default")
      (node (ref "C11") (pin "2") (pinfunction "2_2") (pintype "passive"))
      (node (ref "C25") (pin "2") (pinfunction "2_2") (pintype "passive"))
      (node (ref "R10") (pin "2") (pinfunction "2_2") (pintype "passive"))
      (node (ref "R7") (pin "2") (pinfunction "2_2") (pintype "passive"))
      (node (ref "U39") (pin "A3") (pinfunction "FB_A3") (pintype "input"))
    )
    (net (code "16") (name "PHV") (class "Default")
      (node (ref "C3") (pin "1") (pinfunction "+_1") (pintype "passive"))
      (node (ref "C4") (pin "1") (pinfunction "1_1") (pintype "passive"))
      (node (ref "D3") (pin "1") (pinfunction "K_1") (pintype "passive"))
      (node (ref "J2") (pin "1") (pinfunction "1_1") (pintype "passive"))
      (node (ref "R3") (pin "2") (pinfunction "2_2") (pintype "passive"))
    )
    (net (code "17") (name "VDDM_LV5") (class "Default")
      (node (ref "C20") (pin "2") (pinfunction "-_2") (pintype "passive"))
      (node (ref "C21") (pin "1") (pinfunction "1_1") (pintype "passive"))
      (node (ref "D8") (pin "2") (pinfunction "A_2") (pintype "passive"))
      (node (ref "J3") (pin "3") (pinfunction "3_3") (pintype "passive"))
      (node (ref "TP5") (pin "1") (pintype "passive"))
    )
    (net (code "18") (name "VDDP_LV5") (class "Default")
      (node (ref "C10") (pin "1") (pinfunction "1_1") (pintype "passive"))
      (node (ref "C14") (pin "1") (pinfunction "1_1") (pintype "passive"))
      (node (ref "C16") (pin "1") (pinfunction "1_1") (pintype "passive"))
      (node (ref "C171") (pin "1") (pinfunction "1_1") (pintype "passive"))
      (node (ref "C18") (pin "1") (pinfunction "1_1") (pintype "passive"))
      (node (ref "C9") (pin "1") (pinfunction "+_1") (pintype "passive"))
      (node (ref "D7") (pin "1") (pinfunction "K_1") (pintype "passive"))
      (node (ref "J3") (pin "1") (pinfunction "1_1") (pintype "passive"))
      (node (ref "TP4") (pin "1") (pintype "passive"))
      (node (ref "U2") (pin "1") (pinfunction "IN_1") (pintype "power_in"))
      (node (ref "U2") (pin "3") (pinfunction "EN_3") (pintype "input"))
      (node (ref "U3") (pin "A1") (pinfunction "EN_A1") (pintype "input"))
      (node (ref "U3") (pin "C3") (pinfunction "IN_C3") (pintype "power_in"))
      (node (ref "U34") (pin "A1") (pinfunction "EN_A1") (pintype "input"))
      (node (ref "U34") (pin "C3") (pinfunction "IN_C3") (pintype "power_in"))
      (node (ref "U39") (pin "A1") (pinfunction "EN_A1") (pintype "input"))
      (node (ref "U39") (pin "C3") (pinfunction "IN_C3") (pintype "power_in"))
    )
    (net (code "19") (name "V_1P8") (class "Default")
      (node (ref "C11") (pin "1") (pinfunction "1_1") (pintype "passive"))
      (node (ref "C15") (pin "2") (pinfunction "2_2") (pintype "passive"))
      (node (ref "C25") (pin "1") (pinfunction "1_1") (pintype "passive"))
      (node (ref "D10") (pin "1") (pinfunction "A_1") (pintype "passive"))
      (node (ref "R17") (pin "1") (pinfunction "1_1") (pintype "passive"))
      (node (ref "R170") (pin "1") (pinfunction "1_1") (pintype "passive"))
      (node (ref "R7") (pin "1") (pinfunction "1_1") (pintype "passive"))
      (node (ref "TP1") (pin "1") (pintype "passive"))
      (node (ref "U39") (pin "C1") (pinfunction "OUT_C1") (pintype "power_in"))
    )
    (net (code "20") (name "V_2P5") (class "Default")
      (node (ref "C13") (pin "1") (pinfunction "1_1") (pintype "passive"))
      (node (ref "C19") (pin "1") (pinfunction "1_1") (pintype "passive"))
      (node (ref "D11") (pin "1") (pinfunction "A_1") (pintype "passive"))
      (node (ref "R168") (pin "1") (pinfunction "1_1") (pintype "passive"))
      (node (ref "R9") (pin "2") (pinfunction "2_2") (pintype "passive"))
      (node (ref "TP3") (pin "1") (pintype "passive"))
      (node (ref "U3") (pin "C1") (pinfunction "OUT_C1") (pintype "power_in"))
    )
    (net (code "21") (name "V_3P3") (class "Default")
      (node (ref "D9") (pin "1") (pinfunction "A_1") (pintype "passive"))
      (node (ref "R167") (pin "1") (pinfunction "1_1") (pintype "passive"))
      (node (ref "R248") (pin "2") (pinfunction "2_2") (pintype "passive"))
      (node (ref "R249") (pin "2") (pinfunction "2_2") (pintype "passive"))
      (node (ref "TP2") (pin "1") (pintype "passive"))
    )
  )
)
